# ST_LINK_V3E.net
KiCad netlist of a schematic drawn in Altium Designer
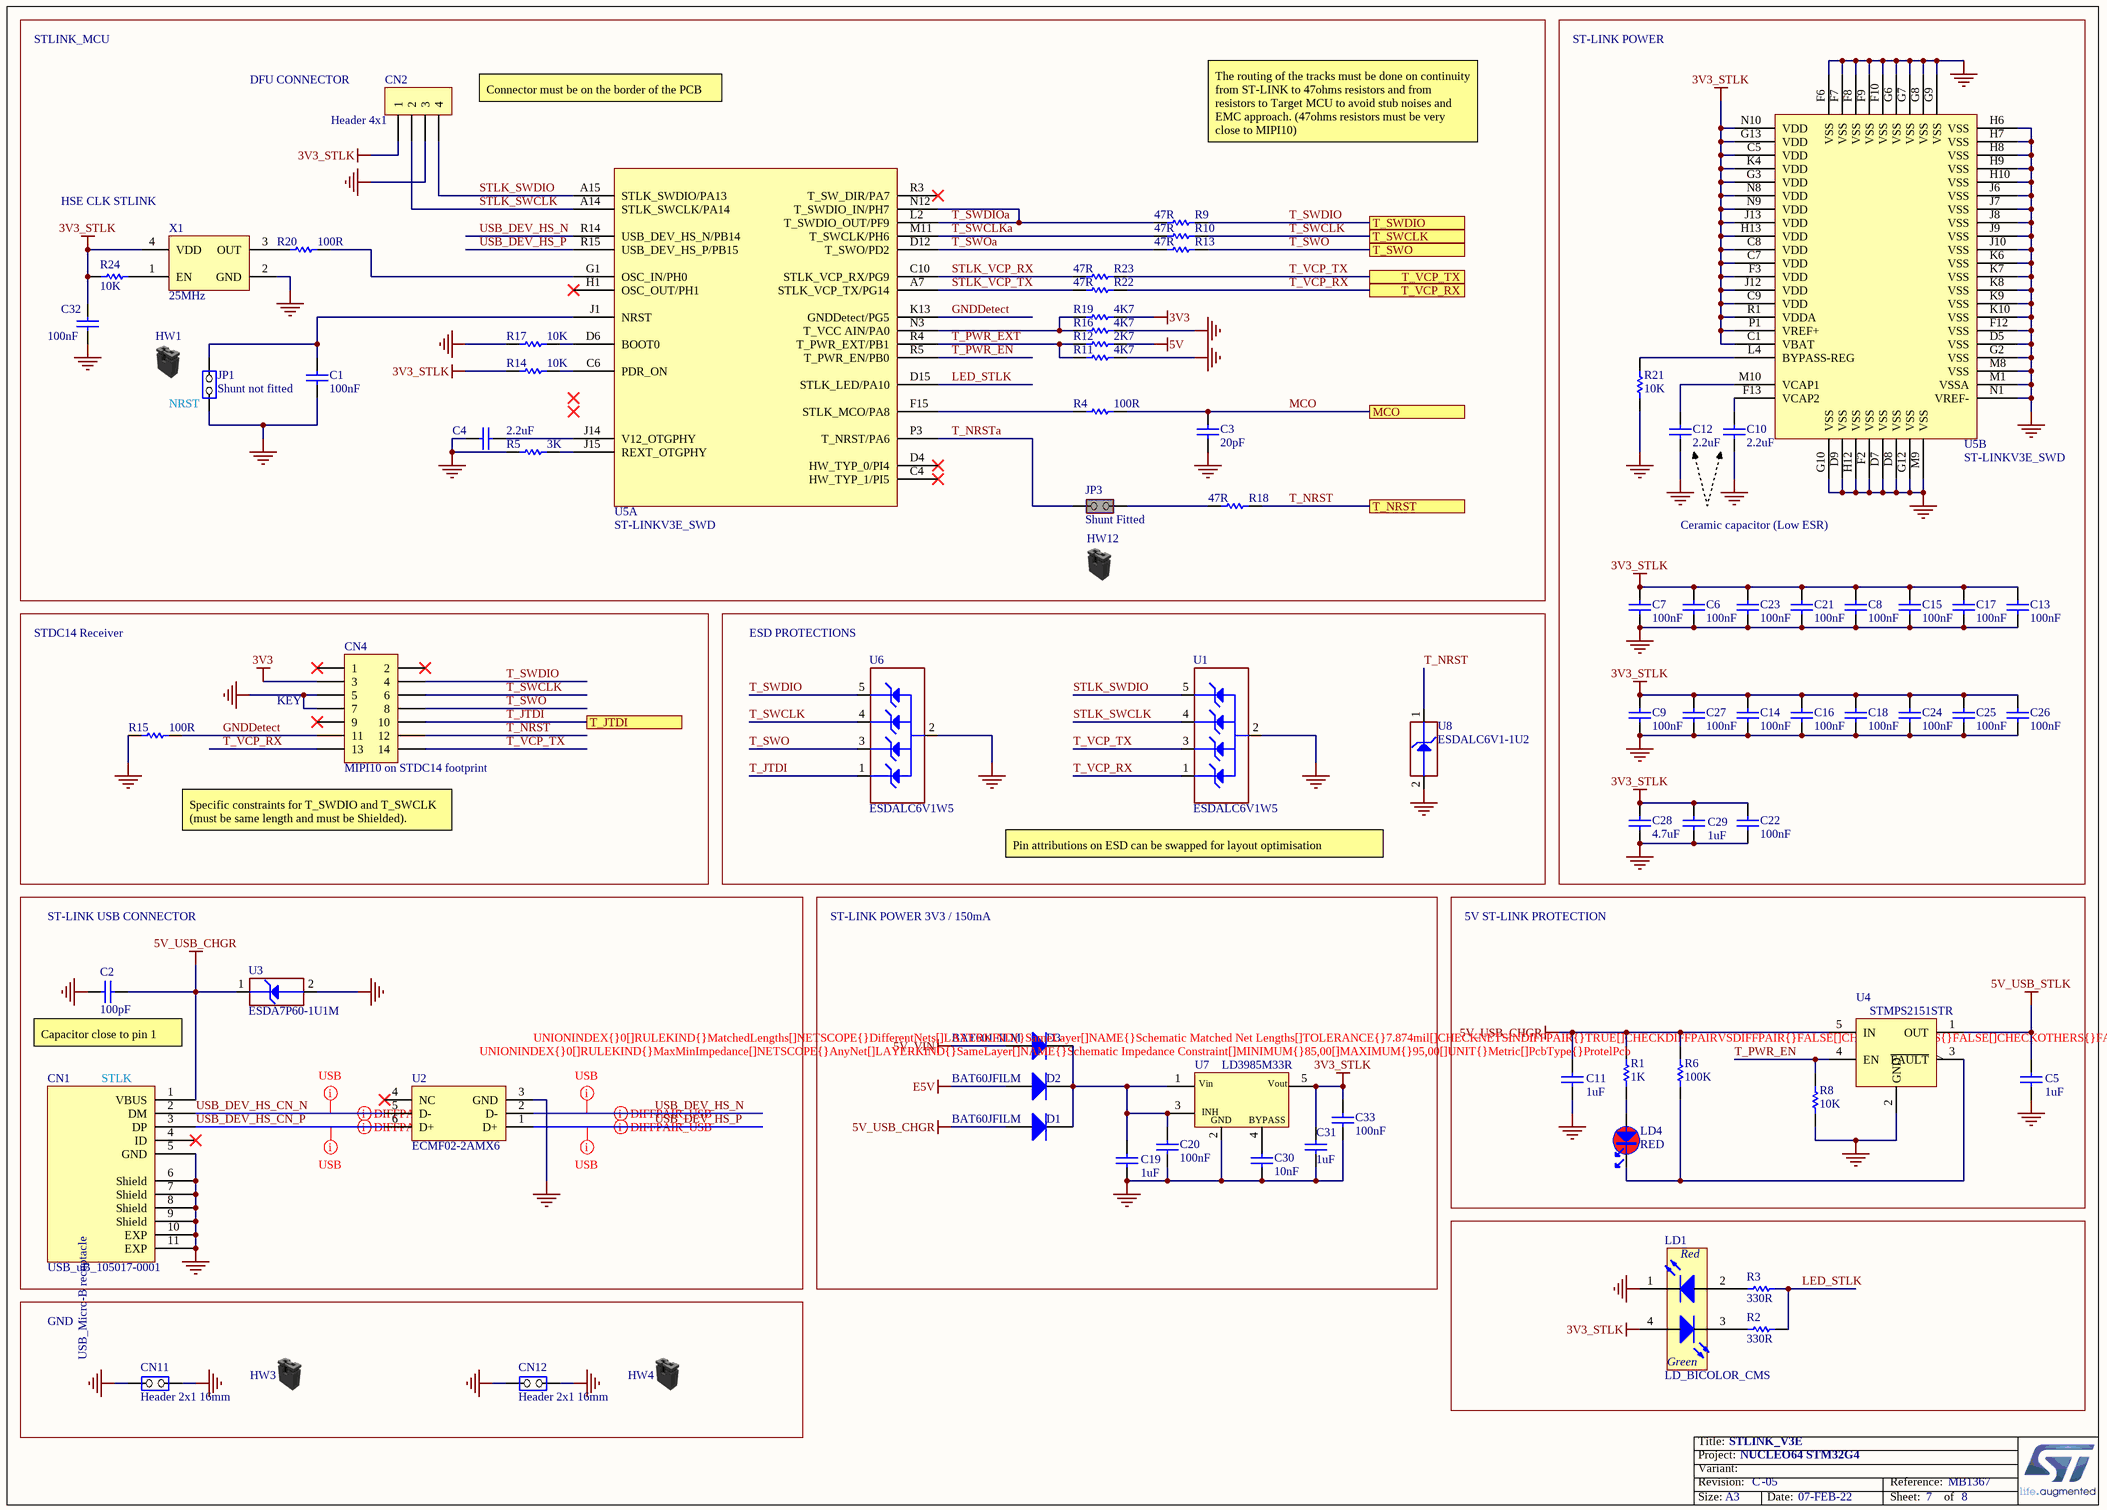
[diagram p0: ST_LINK_V3E.SchDoc]

(export (version "E")
  (design (tool "Eeschema 10.0.6"))
  (components
    (comp (ref "C1")
      (value "100nF")
      (footprint "C0402")
      (description "Capacitor, MLCC, 100nF, 16V, X7R, 10%, 0402, T=0,5mm")
      (fields
        (field (name "INTERNAL_PART_NUMBER") "MCD-00102")
        (field (name "MANUFACTURER_PART_NUMBER") "CC0402KRX7R7BB104")
      )
      (libsource (lib "MCD_PARTS_database") (part "Capacitor"))
    )
    (comp (ref "C2")
      (value "100pF")
      (footprint "C0402")
      (description "Capacitor, MLCC, 100pF, 50V, NPO, 5%, 0402, T=0,5mm")
      (fields
        (field (name "INTERNAL_PART_NUMBER") "MCD-00205")
        (field (name "MANUFACTURER_PART_NUMBER") "CC0402JRNPO9BN101")
      )
      (libsource (lib "MCD_PARTS_database") (part "Capacitor"))
    )
    (comp (ref "C3")
      (value "20pF")
      (footprint "C0402")
      (description "Capacitor, MLCC, 20pF, 50V, NPO, 5%, 0402, T=0,5mm")
      (fields
        (field (name "INTERNAL_PART_NUMBER") "MCD-00016")
        (field (name "MANUFACTURER_PART_NUMBER") "CC0402JRNPO9BN200")
      )
      (libsource (lib "MCD_PARTS_database") (part "Capacitor"))
    )
    (comp (ref "C4")
      (value "2.2uF")
      (footprint "C0603")
      (description "Capacitor, MLCC, 2.2uF, 10V, X5R, 10%, 0603, T=0,8mm")
      (fields
        (field (name "INTERNAL_PART_NUMBER") "MCD-00012")
        (field (name "MANUFACTURER_PART_NUMBER") "CC0603KRX5R6BB225")
      )
      (libsource (lib "MCD_PARTS_database") (part "Capacitor"))
    )
    (comp (ref "C5")
      (value "1uF")
      (footprint "C0603")
      (description "Capacitor, MLCC, 1uF, 16V, X5R, 10%, 0603, T=0,8mm")
      (fields
        (field (name "INTERNAL_PART_NUMBER") "MCD-00010")
        (field (name "MANUFACTURER_PART_NUMBER") "CC0603KRX5R7BB105")
      )
      (libsource (lib "MCD_PARTS_database") (part "Capacitor"))
    )
    (comp (ref "C6")
      (value "100nF")
      (footprint "C0402")
      (description "Capacitor, MLCC, 100nF, 16V, X7R, 10%, 0402, T=0,5mm")
      (fields
        (field (name "INTERNAL_PART_NUMBER") "MCD-00102")
        (field (name "MANUFACTURER_PART_NUMBER") "CC0402KRX7R7BB104")
      )
      (libsource (lib "MCD_PARTS_database") (part "Capacitor"))
    )
    (comp (ref "C7")
      (value "100nF")
      (footprint "C0402")
      (description "Capacitor, MLCC, 100nF, 16V, X7R, 10%, 0402, T=0,5mm")
      (fields
        (field (name "INTERNAL_PART_NUMBER") "MCD-00102")
        (field (name "MANUFACTURER_PART_NUMBER") "CC0402KRX7R7BB104")
      )
      (libsource (lib "MCD_PARTS_database") (part "Capacitor"))
    )
    (comp (ref "C8")
      (value "100nF")
      (footprint "C0402")
      (description "Capacitor, MLCC, 100nF, 16V, X7R, 10%, 0402, T=0,5mm")
      (fields
        (field (name "INTERNAL_PART_NUMBER") "MCD-00102")
        (field (name "MANUFACTURER_PART_NUMBER") "CC0402KRX7R7BB104")
      )
      (libsource (lib "MCD_PARTS_database") (part "Capacitor"))
    )
    (comp (ref "C9")
      (value "100nF")
      (footprint "C0402")
      (description "Capacitor, MLCC, 100nF, 16V, X7R, 10%, 0402, T=0,5mm")
      (fields
        (field (name "INTERNAL_PART_NUMBER") "MCD-00102")
        (field (name "MANUFACTURER_PART_NUMBER") "CC0402KRX7R7BB104")
      )
      (libsource (lib "MCD_PARTS_database") (part "Capacitor"))
    )
    (comp (ref "C10")
      (value "2.2uF")
      (footprint "C1206_H1P15")
      (description "Capacitor, MLCC, 2.2uF, 16V, X7R, 10%, 1206, T=1,15mm")
      (fields
        (field (name "INTERNAL_PART_NUMBER") "MCD-00008")
        (field (name "MANUFACTURER_PART_NUMBER") "CC1206KKX7R7BB225")
      )
      (libsource (lib "MCD_PARTS_database") (part "Capacitor"))
    )
    (comp (ref "C11")
      (value "1uF")
      (footprint "C0603")
      (description "Capacitor, MLCC, 1uF, 16V, X5R, 10%, 0603, T=0,8mm")
      (fields
        (field (name "INTERNAL_PART_NUMBER") "MCD-00010")
        (field (name "MANUFACTURER_PART_NUMBER") "CC0603KRX5R7BB105")
      )
      (libsource (lib "MCD_PARTS_database") (part "Capacitor"))
    )
    (comp (ref "C12")
      (value "2.2uF")
      (footprint "C1206_H1P15")
      (description "Capacitor, MLCC, 2.2uF, 16V, X7R, 10%, 1206, T=1,15mm")
      (fields
        (field (name "INTERNAL_PART_NUMBER") "MCD-00008")
        (field (name "MANUFACTURER_PART_NUMBER") "CC1206KKX7R7BB225")
      )
      (libsource (lib "MCD_PARTS_database") (part "Capacitor"))
    )
    (comp (ref "C13")
      (value "100nF")
      (footprint "C0402")
      (description "Capacitor, MLCC, 100nF, 16V, X7R, 10%, 0402, T=0,5mm")
      (fields
        (field (name "INTERNAL_PART_NUMBER") "MCD-00102")
        (field (name "MANUFACTURER_PART_NUMBER") "CC0402KRX7R7BB104")
      )
      (libsource (lib "MCD_PARTS_database") (part "Capacitor"))
    )
    (comp (ref "C14")
      (value "100nF")
      (footprint "C0402")
      (description "Capacitor, MLCC, 100nF, 16V, X7R, 10%, 0402, T=0,5mm")
      (fields
        (field (name "INTERNAL_PART_NUMBER") "MCD-00102")
        (field (name "MANUFACTURER_PART_NUMBER") "CC0402KRX7R7BB104")
      )
      (libsource (lib "MCD_PARTS_database") (part "Capacitor"))
    )
    (comp (ref "C15")
      (value "100nF")
      (footprint "C0402")
      (description "Capacitor, MLCC, 100nF, 16V, X7R, 10%, 0402, T=0,5mm")
      (fields
        (field (name "INTERNAL_PART_NUMBER") "MCD-00102")
        (field (name "MANUFACTURER_PART_NUMBER") "CC0402KRX7R7BB104")
      )
      (libsource (lib "MCD_PARTS_database") (part "Capacitor"))
    )
    (comp (ref "C16")
      (value "100nF")
      (footprint "C0402")
      (description "Capacitor, MLCC, 100nF, 16V, X7R, 10%, 0402, T=0,5mm")
      (fields
        (field (name "INTERNAL_PART_NUMBER") "MCD-00102")
        (field (name "MANUFACTURER_PART_NUMBER") "CC0402KRX7R7BB104")
      )
      (libsource (lib "MCD_PARTS_database") (part "Capacitor"))
    )
    (comp (ref "C17")
      (value "100nF")
      (footprint "C0402")
      (description "Capacitor, MLCC, 100nF, 16V, X7R, 10%, 0402, T=0,5mm")
      (fields
        (field (name "INTERNAL_PART_NUMBER") "MCD-00102")
        (field (name "MANUFACTURER_PART_NUMBER") "CC0402KRX7R7BB104")
      )
      (libsource (lib "MCD_PARTS_database") (part "Capacitor"))
    )
    (comp (ref "C18")
      (value "100nF")
      (footprint "C0402")
      (description "Capacitor, MLCC, 100nF, 16V, X7R, 10%, 0402, T=0,5mm")
      (fields
        (field (name "INTERNAL_PART_NUMBER") "MCD-00102")
        (field (name "MANUFACTURER_PART_NUMBER") "CC0402KRX7R7BB104")
      )
      (libsource (lib "MCD_PARTS_database") (part "Capacitor"))
    )
    (comp (ref "C19")
      (value "1uF")
      (footprint "C0603")
      (description "Capacitor, MLCC, 1uF, 16V, X5R, 10%, 0603, T=0,8mm")
      (fields
        (field (name "INTERNAL_PART_NUMBER") "MCD-00010")
        (field (name "MANUFACTURER_PART_NUMBER") "CC0603KRX5R7BB105")
      )
      (libsource (lib "MCD_PARTS_database") (part "Capacitor"))
    )
    (comp (ref "C20")
      (value "100nF")
      (footprint "C0402")
      (description "Capacitor, MLCC, 100nF, 16V, X7R, 10%, 0402, T=0,5mm")
      (fields
        (field (name "INTERNAL_PART_NUMBER") "MCD-00102")
        (field (name "MANUFACTURER_PART_NUMBER") "CC0402KRX7R7BB104")
      )
      (libsource (lib "MCD_PARTS_database") (part "Capacitor"))
    )
    (comp (ref "C21")
      (value "100nF")
      (footprint "C0402")
      (description "Capacitor, MLCC, 100nF, 16V, X7R, 10%, 0402, T=0,5mm")
      (fields
        (field (name "INTERNAL_PART_NUMBER") "MCD-00102")
        (field (name "MANUFACTURER_PART_NUMBER") "CC0402KRX7R7BB104")
      )
      (libsource (lib "MCD_PARTS_database") (part "Capacitor"))
    )
    (comp (ref "C22")
      (value "100nF")
      (footprint "C0402")
      (description "Capacitor, MLCC, 100nF, 16V, X7R, 10%, 0402, T=0,5mm")
      (fields
        (field (name "INTERNAL_PART_NUMBER") "MCD-00102")
        (field (name "MANUFACTURER_PART_NUMBER") "CC0402KRX7R7BB104")
      )
      (libsource (lib "MCD_PARTS_database") (part "Capacitor"))
    )
    (comp (ref "C23")
      (value "100nF")
      (footprint "C0402")
      (description "Capacitor, MLCC, 100nF, 16V, X7R, 10%, 0402, T=0,5mm")
      (fields
        (field (name "INTERNAL_PART_NUMBER") "MCD-00102")
        (field (name "MANUFACTURER_PART_NUMBER") "CC0402KRX7R7BB104")
      )
      (libsource (lib "MCD_PARTS_database") (part "Capacitor"))
    )
    (comp (ref "C24")
      (value "100nF")
      (footprint "C0402")
      (description "Capacitor, MLCC, 100nF, 16V, X7R, 10%, 0402, T=0,5mm")
      (fields
        (field (name "INTERNAL_PART_NUMBER") "MCD-00102")
        (field (name "MANUFACTURER_PART_NUMBER") "CC0402KRX7R7BB104")
      )
      (libsource (lib "MCD_PARTS_database") (part "Capacitor"))
    )
    (comp (ref "C25")
      (value "100nF")
      (footprint "C0402")
      (description "Capacitor, MLCC, 100nF, 16V, X7R, 10%, 0402, T=0,5mm")
      (fields
        (field (name "INTERNAL_PART_NUMBER") "MCD-00102")
        (field (name "MANUFACTURER_PART_NUMBER") "CC0402KRX7R7BB104")
      )
      (libsource (lib "MCD_PARTS_database") (part "Capacitor"))
    )
    (comp (ref "C26")
      (value "100nF")
      (footprint "C0402")
      (description "Capacitor, MLCC, 100nF, 16V, X7R, 10%, 0402, T=0,5mm")
      (fields
        (field (name "INTERNAL_PART_NUMBER") "MCD-00102")
        (field (name "MANUFACTURER_PART_NUMBER") "CC0402KRX7R7BB104")
      )
      (libsource (lib "MCD_PARTS_database") (part "Capacitor"))
    )
    (comp (ref "C27")
      (value "100nF")
      (footprint "C0402")
      (description "Capacitor, MLCC, 100nF, 16V, X7R, 10%, 0402, T=0,5mm")
      (fields
        (field (name "INTERNAL_PART_NUMBER") "MCD-00102")
        (field (name "MANUFACTURER_PART_NUMBER") "CC0402KRX7R7BB104")
      )
      (libsource (lib "MCD_PARTS_database") (part "Capacitor"))
    )
    (comp (ref "C28")
      (value "4.7uF")
      (footprint "C0603")
      (description "Capacitor, MLCC, 4.7uF, 16V, X5R, 10%, 0603, T=0.8mm")
      (fields
        (field (name "INTERNAL_PART_NUMBER") "MCD-00009")
        (field (name "MANUFACTURER_PART_NUMBER") "CC0603KRX5R7BB475")
      )
      (libsource (lib "MCD_PARTS_database") (part "Capacitor"))
    )
    (comp (ref "C29")
      (value "1uF")
      (footprint "C0603")
      (description "Capacitor, MLCC, 1uF, 16V, X5R, 10%, 0603, T=0,8mm")
      (fields
        (field (name "INTERNAL_PART_NUMBER") "MCD-00010")
        (field (name "MANUFACTURER_PART_NUMBER") "CC0603KRX5R7BB105")
      )
      (libsource (lib "MCD_PARTS_database") (part "Capacitor"))
    )
    (comp (ref "C30")
      (value "10nF")
      (footprint "C0402")
      (description "Capacitor, MLCC, 10nF, 16V, X7R, 10%, 0402, T=0.5mm")
      (fields
        (field (name "INTERNAL_PART_NUMBER") "MCD-00011")
        (field (name "MANUFACTURER_PART_NUMBER") "CC0402KRX7R7BB103")
      )
      (libsource (lib "MCD_PARTS_database") (part "Capacitor"))
    )
    (comp (ref "C31")
      (value "1uF")
      (footprint "C0603")
      (description "Capacitor, MLCC, 1uF, 16V, X5R, 10%, 0603, T=0,8mm")
      (fields
        (field (name "INTERNAL_PART_NUMBER") "MCD-00010")
        (field (name "MANUFACTURER_PART_NUMBER") "CC0603KRX5R7BB105")
      )
      (libsource (lib "MCD_PARTS_database") (part "Capacitor"))
    )
    (comp (ref "C32")
      (value "100nF")
      (footprint "C0402")
      (description "Capacitor, MLCC, 100nF, 16V, X7R, 10%, 0402, T=0,5mm")
      (fields
        (field (name "INTERNAL_PART_NUMBER") "MCD-00102")
        (field (name "MANUFACTURER_PART_NUMBER") "CC0402KRX7R7BB104")
      )
      (libsource (lib "MCD_PARTS_database") (part "Capacitor"))
    )
    (comp (ref "C33")
      (value "100nF")
      (footprint "C0402")
      (description "Capacitor, MLCC, 100nF, 16V, X7R, 10%, 0402, T=0,5mm")
      (fields
        (field (name "INTERNAL_PART_NUMBER") "MCD-00102")
        (field (name "MANUFACTURER_PART_NUMBER") "CC0402KRX7R7BB104")
      )
      (libsource (lib "MCD_PARTS_database") (part "Capacitor"))
    )
    (comp (ref "CN1")
      (value "USB_uB_105017-0001")
      (footprint "CON_USBMICROB_MOLEX_105017-0001_H2P90")
      (description "USB-MICRO-B, 0.65mm, RA, SMT, Bottom Mount,")
      (fields
        (field (name "INTERNAL_PART_NUMBER") "MCD-00028")
        (field (name "MANUFACTURER_PART_NUMBER") "1050170001")
      )
      (libsource (lib "MCD_PARTS_database") (part "USB_uB_105017.0001"))
    )
    (comp (ref "CN2")
      (value "Header 4x1")
      (footprint "CON_SAMTEC_TSW-104-07-G-S")
      (description "Header, 4x1, 2,54mm, VR, TH, Height 5.84mm/2.54mm")
      (fields
        (field (name "INTERNAL_PART_NUMBER") "MCD-00029")
        (field (name "MANUFACTURER_PART_NUMBER") "TSW-104-07-x-S")
      )
      (libsource (lib "MCD_PARTS_database") (part "Header 4x1"))
    )
    (comp (ref "CN4")
      (value "MIPI10 on STDC14 footprint")
      (footprint "CON_STDC14_Receiver_MEDIUM_WITH_MIPI10_3D")
      (fields
        (field (name "INTERNAL_PART_NUMBER") "MCD-01226")
        (field (name "MANUFACTURER_PART_NUMBER") "FTSH-105-01-L-DV-K")
        (field (name "MANUFACTURER") "SAMTEC")
      )
      (libsource (lib "MCD_PARTS_database") (part "Header 7x2"))
    )
    (comp (ref "CN11")
      (value "Header 2x1 16mm")
      (footprint "CON_SAMTEC_TSW-102-09-X-S")
      (description "Header, 2x1, 2,54mm, VR, TH, Height 5.84mm/10.16mm")
      (fields
        (field (name "INTERNAL_PART_NUMBER") "MCD-00214")
        (field (name "MANUFACTURER_PART_NUMBER") "TSW-102-09-x-S")
      )
      (libsource (lib "MCD_PARTS_database") (part "Jumper_Header 2x1"))
    )
    (comp (ref "CN12")
      (value "Header 2x1 16mm")
      (footprint "CON_SAMTEC_TSW-102-09-X-S")
      (description "Header, 2x1, 2,54mm, VR, TH, Height 5.84mm/10.16mm")
      (fields
        (field (name "INTERNAL_PART_NUMBER") "MCD-00214")
        (field (name "MANUFACTURER_PART_NUMBER") "TSW-102-09-x-S")
      )
      (libsource (lib "MCD_PARTS_database") (part "Jumper_Header 2x1"))
    )
    (comp (ref "D1")
      (value "BAT60JFILM")
      (footprint "DIO_SOD323")
      (fields
        (field (name "INTERNAL_PART_NUMBER") "MCD-00034")
        (field (name "MANUFACTURER") "STMICROELECTRONICS")
      )
      (libsource (lib "MCD_PARTS_database") (part "BAT60JFILM"))
    )
    (comp (ref "D2")
      (value "BAT60JFILM")
      (footprint "DIO_SOD323")
      (fields
        (field (name "INTERNAL_PART_NUMBER") "MCD-00034")
        (field (name "MANUFACTURER") "STMICROELECTRONICS")
      )
      (libsource (lib "MCD_PARTS_database") (part "BAT60JFILM"))
    )
    (comp (ref "D3")
      (value "BAT60JFILM")
      (footprint "DIO_SOD323")
      (fields
        (field (name "INTERNAL_PART_NUMBER") "MCD-00034")
        (field (name "MANUFACTURER") "STMICROELECTRONICS")
      )
      (libsource (lib "MCD_PARTS_database") (part "BAT60JFILM"))
    )
    (comp (ref "HW1")
      (value "~")
      (description "SHUNT 2.54mm BLACK")
      (fields
        (field (name "INTERNAL_PART_NUMBER") "MCD-00043")
        (field (name "MANUFACTURER_PART_NUMBER") "SNT-100-BK-G")
      )
      (libsource (lib "MCD_PARTS_database") (part "Shunt Black 2.54mm"))
    )
    (comp (ref "HW3")
      (value "~")
      (description "SHUNT 2.54mm BLACK")
      (fields
        (field (name "INTERNAL_PART_NUMBER") "MCD-00043")
        (field (name "MANUFACTURER_PART_NUMBER") "SNT-100-BK-G")
      )
      (libsource (lib "MCD_PARTS_database") (part "Shunt Black 2.54mm"))
    )
    (comp (ref "HW4")
      (value "~")
      (description "SHUNT 2.54mm BLACK")
      (fields
        (field (name "INTERNAL_PART_NUMBER") "MCD-00043")
        (field (name "MANUFACTURER_PART_NUMBER") "SNT-100-BK-G")
      )
      (libsource (lib "MCD_PARTS_database") (part "Shunt Black 2.54mm"))
    )
    (comp (ref "HW12")
      (value "~")
      (description "SHUNT 2.54mm BLACK")
      (fields
        (field (name "INTERNAL_PART_NUMBER") "MCD-00043")
        (field (name "MANUFACTURER_PART_NUMBER") "SNT-100-BK-G")
      )
      (libsource (lib "MCD_PARTS_database") (part "Shunt Black 2.54mm"))
    )
    (comp (ref "JP1")
      (value "Shunt not fitted")
      (footprint "CON_SAMTEC_TSW-102-07-G-S")
      (description "Header, 2x1, 2,54mm, VR, TH, Height 5.84mm/2.54mm")
      (fields
        (field (name "INTERNAL_PART_NUMBER") "MCD-00045")
        (field (name "MANUFACTURER_PART_NUMBER") "TSW-102-07-x-S")
      )
      (libsource (lib "MCD_PARTS_database") (part "Jumper_Header 2x1"))
    )
    (comp (ref "JP3")
      (value "Shunt Fitted")
      (footprint "CON_SAMTEC_TSW-102-07-G-S")
      (description "Header, 2x1, 2,54mm, VR, TH, Height 5.84mm/2.54mm - Shunt Fitted by default")
      (fields
        (field (name "INTERNAL_PART_NUMBER") "MCD-00683")
        (field (name "MANUFACTURER_PART_NUMBER") "TSW-102-07-x-S")
      )
      (libsource (lib "MCD_PARTS_database") (part "Jumper_Header 2x1 Fitted"))
    )
    (comp (ref "LD1")
      (value "LD_BICOLOR_CMS")
      (footprint "LED_BI-GR_HSMF-A201-A00J1")
      (description "LED Bicolor")
      (fields (field (name "INTERNAL_PART_NUMBER") "MCD-02402") (field (name "MANUFACTURER") "EVERLIGHT"))
      (libsource (lib "MCD_PARTS_database") (part "LD_BICOLOR_CMS"))
    )
    (comp (ref "LD4")
      (value "RED")
      (footprint "LED_0603_RED_H0P4")
      (description "LED, Red, VF : Min=1.7V , Max=2.2V, IF : 25mA, 0603 SMD")
      (fields (field (name "INTERNAL_PART_NUMBER") "MCD-02787") (field (name "MANUFACTURER") "EVERLIGHT"))
      (libsource (lib "MCD_PARTS_database") (part "LED_red"))
    )
    (comp (ref "R1")
      (value "1K")
      (footprint "R0603")
      (description "Resistor,1K,0603,1%,1/10W")
      (fields
        (field (name "INTERNAL_PART_NUMBER") "MCD-00070")
        (field (name "MANUFACTURER_PART_NUMBER") "RC0603FR-071KL")
      )
      (libsource (lib "MCD_PARTS_database") (part "Resistor"))
    )
    (comp (ref "R2")
      (value "330R")
      (footprint "R0603")
      (description "Resistor,330R,0603,1%,1/10W")
      (fields
        (field (name "INTERNAL_PART_NUMBER") "MCD-00197")
        (field (name "MANUFACTURER_PART_NUMBER") "RC0603FR-07330RL")
      )
      (libsource (lib "MCD_PARTS_database") (part "Resistor"))
    )
    (comp (ref "R3")
      (value "330R")
      (footprint "R0603")
      (description "Resistor,330R,0603,1%,1/10W")
      (fields
        (field (name "INTERNAL_PART_NUMBER") "MCD-00197")
        (field (name "MANUFACTURER_PART_NUMBER") "RC0603FR-07330RL")
      )
      (libsource (lib "MCD_PARTS_database") (part "Resistor"))
    )
    (comp (ref "R4")
      (value "100R")
      (footprint "R0402")
      (description "Resistor,100R,0402,1%,1/16W")
      (fields
        (field (name "INTERNAL_PART_NUMBER") "MCD-00119")
        (field (name "MANUFACTURER_PART_NUMBER") "RC0402FR-07100RL")
      )
      (libsource (lib "MCD_PARTS_database") (part "Resistor"))
    )
    (comp (ref "R5")
      (value "3K")
      (footprint "R0402")
      (description "Resistor,3K,0402,1%,1/16W")
      (fields
        (field (name "INTERNAL_PART_NUMBER") "MCD-00185")
        (field (name "MANUFACTURER_PART_NUMBER") "RC0402FR-073KL")
      )
      (libsource (lib "MCD_PARTS_database") (part "Resistor"))
    )
    (comp (ref "R6")
      (value "100K")
      (footprint "R0603")
      (description "Resistor,100K,0603,1%,1/10W")
      (fields
        (field (name "INTERNAL_PART_NUMBER") "MCD-00223")
        (field (name "MANUFACTURER_PART_NUMBER") "RC0603FR-07100KL")
      )
      (libsource (lib "MCD_PARTS_database") (part "Resistor"))
    )
    (comp (ref "R8")
      (value "10K")
      (footprint "R0603")
      (description "Resistor,10K,0603,1%,1/10W")
      (fields
        (field (name "INTERNAL_PART_NUMBER") "MCD-00220")
        (field (name "MANUFACTURER_PART_NUMBER") "RC0603FR-0710KL")
      )
      (libsource (lib "MCD_PARTS_database") (part "Resistor"))
    )
    (comp (ref "R9")
      (value "47R")
      (footprint "R0402")
      (description "Resistor,47R,0402,1%,1/16W")
      (fields
        (field (name "INTERNAL_PART_NUMBER") "MCD-00481")
        (field (name "MANUFACTURER_PART_NUMBER") "RC0402FR-0747RL")
      )
      (libsource (lib "MCD_PARTS_database") (part "Resistor"))
    )
    (comp (ref "R10")
      (value "47R")
      (footprint "R0402")
      (description "Resistor,47R,0402,1%,1/16W")
      (fields
        (field (name "INTERNAL_PART_NUMBER") "MCD-00481")
        (field (name "MANUFACTURER_PART_NUMBER") "RC0402FR-0747RL")
      )
      (libsource (lib "MCD_PARTS_database") (part "Resistor"))
    )
    (comp (ref "R11")
      (value "4K7")
      (footprint "R0402")
      (description "Resistor,4K7,0402,1%,1/16W")
      (fields
        (field (name "INTERNAL_PART_NUMBER") "MCD-00065")
        (field (name "MANUFACTURER_PART_NUMBER") "RC0402FR-074K7L")
      )
      (libsource (lib "MCD_PARTS_database") (part "Resistor"))
    )
    (comp (ref "R12")
      (value "2K7")
      (footprint "R0402")
      (description "Resistor,2K7,0402,1%,1/16W")
      (fields
        (field (name "INTERNAL_PART_NUMBER") "MCD-00055")
        (field (name "MANUFACTURER_PART_NUMBER") "RC0402FR-072K7L")
      )
      (libsource (lib "MCD_PARTS_database") (part "Resistor"))
    )
    (comp (ref "R13")
      (value "47R")
      (footprint "R0402")
      (description "Resistor,47R,0402,1%,1/16W")
      (fields
        (field (name "INTERNAL_PART_NUMBER") "MCD-00481")
        (field (name "MANUFACTURER_PART_NUMBER") "RC0402FR-0747RL")
      )
      (libsource (lib "MCD_PARTS_database") (part "Resistor"))
    )
    (comp (ref "R14")
      (value "10K")
      (footprint "R0402")
      (description "Resistor,10K,0402,1%,1/16W")
      (fields
        (field (name "INTERNAL_PART_NUMBER") "MCD-00053")
        (field (name "MANUFACTURER_PART_NUMBER") "RC0402FR-0710KL")
      )
      (libsource (lib "MCD_PARTS_database") (part "Resistor"))
    )
    (comp (ref "R15")
      (value "100R")
      (footprint "R0402")
      (description "Resistor,100R,0402,1%,1/16W")
      (fields
        (field (name "INTERNAL_PART_NUMBER") "MCD-00119")
        (field (name "MANUFACTURER_PART_NUMBER") "RC0402FR-07100RL")
      )
      (libsource (lib "MCD_PARTS_database") (part "Resistor"))
    )
    (comp (ref "R16")
      (value "4K7")
      (footprint "R0402")
      (description "Resistor,4K7,0402,1%,1/16W")
      (fields
        (field (name "INTERNAL_PART_NUMBER") "MCD-00065")
        (field (name "MANUFACTURER_PART_NUMBER") "RC0402FR-074K7L")
      )
      (libsource (lib "MCD_PARTS_database") (part "Resistor"))
    )
    (comp (ref "R17")
      (value "10K")
      (footprint "R0402")
      (description "Resistor,10K,0402,1%,1/16W")
      (fields
        (field (name "INTERNAL_PART_NUMBER") "MCD-00053")
        (field (name "MANUFACTURER_PART_NUMBER") "RC0402FR-0710KL")
      )
      (libsource (lib "MCD_PARTS_database") (part "Resistor"))
    )
    (comp (ref "R18")
      (value "47R")
      (footprint "R0402")
      (description "Resistor,47R,0402,1%,1/16W")
      (fields
        (field (name "INTERNAL_PART_NUMBER") "MCD-00481")
        (field (name "MANUFACTURER_PART_NUMBER") "RC0402FR-0747RL")
      )
      (libsource (lib "MCD_PARTS_database") (part "Resistor"))
    )
    (comp (ref "R19")
      (value "4K7")
      (footprint "R0402")
      (description "Resistor,4K7,0402,1%,1/16W")
      (fields
        (field (name "INTERNAL_PART_NUMBER") "MCD-00065")
        (field (name "MANUFACTURER_PART_NUMBER") "RC0402FR-074K7L")
      )
      (libsource (lib "MCD_PARTS_database") (part "Resistor"))
    )
    (comp (ref "R20")
      (value "100R")
      (footprint "R0402")
      (description "Resistor,100R,0402,1%,1/16W")
      (fields
        (field (name "INTERNAL_PART_NUMBER") "MCD-00119")
        (field (name "MANUFACTURER_PART_NUMBER") "RC0402FR-07100RL")
      )
      (libsource (lib "MCD_PARTS_database") (part "Resistor"))
    )
    (comp (ref "R21")
      (value "10K")
      (footprint "R0402")
      (description "Resistor,10K,0402,1%,1/16W")
      (fields
        (field (name "INTERNAL_PART_NUMBER") "MCD-00053")
        (field (name "MANUFACTURER_PART_NUMBER") "RC0402FR-0710KL")
      )
      (libsource (lib "MCD_PARTS_database") (part "Resistor"))
    )
    (comp (ref "R22")
      (value "47R")
      (footprint "R0402")
      (description "Resistor,47R,0402,1%,1/16W")
      (fields
        (field (name "INTERNAL_PART_NUMBER") "MCD-00481")
        (field (name "MANUFACTURER_PART_NUMBER") "RC0402FR-0747RL")
      )
      (libsource (lib "MCD_PARTS_database") (part "Resistor"))
    )
    (comp (ref "R23")
      (value "47R")
      (footprint "R0402")
      (description "Resistor,47R,0402,1%,1/16W")
      (fields
        (field (name "INTERNAL_PART_NUMBER") "MCD-00481")
        (field (name "MANUFACTURER_PART_NUMBER") "RC0402FR-0747RL")
      )
      (libsource (lib "MCD_PARTS_database") (part "Resistor"))
    )
    (comp (ref "R24")
      (value "10K")
      (footprint "R0402")
      (description "Resistor,10K,0402,1%,1/16W")
      (fields
        (field (name "INTERNAL_PART_NUMBER") "MCD-00053")
        (field (name "MANUFACTURER_PART_NUMBER") "RC0402FR-0710KL")
      )
      (libsource (lib "MCD_PARTS_database") (part "Resistor"))
    )
    (comp (ref "U1")
      (value "ESDALC6V1W5")
      (footprint "ESD_SOT323-5L")
      (description "Dual Transil array for ESD protection")
      (fields
        (field (name "INTERNAL_PART_NUMBER") "MCD-00136")
        (field (name "MANUFACTURER") "STMICROELECTRONICS")
      )
      (libsource (lib "MCD_PARTS_database") (part "ESDALC6V1W5"))
    )
    (comp (ref "U2")
      (value "ECMF02-2AMX6")
      (footprint "ESD_QFN-6L_1P7X1P5_P050")
      (description "Common mode filter with ESD protection for USB 2.0 interface")
      (fields
        (field (name "INTERNAL_PART_NUMBER") "MCD-00649")
        (field (name "MANUFACTURER") "STMICROELECTRONICS")
      )
      (libsource (lib "MCD_PARTS_database") (part "ECMF02-2AMX6"))
    )
    (comp (ref "U3")
      (value "ESDA7P60-1U1M")
      (footprint "ESD_QFN2_1P6X1_P125")
      (description "High power transient voltage suppressor, 7V breakdown")
      (fields
        (field (name "INTERNAL_PART_NUMBER") "MCD-00251")
        (field (name "MANUFACTURER") "STMICROELECTRONICS")
      )
      (libsource (lib "") (part "ESD-TRANSIL_1"))
    )
    (comp (ref "U4")
      (value "STMPS2151STR")
      (footprint "MOS_SOT23-5L")
      (description "500mA, Enhanced single channel power switches with active high enable pin")
      (fields
        (field (name "INTERNAL_PART_NUMBER") "MCD-00159")
        (field (name "MANUFACTURER") "STMICROELECTRONICS")
      )
      (libsource (lib "MCD_PARTS_database") (part "STMPS2151STR"))
    )
    (comp (ref "U5")
      (value "ST-LINKV3E_SWD")
      (footprint "ICC_UFBGA201_176+25_10X10_P065")
      (description "STM32F723IEK  (STM32F7) BGA176")
      (fields
        (field (name "INTERNAL_PART_NUMBER") "MCD-00596")
        (field (name "MANUFACTURER_PART_NUMBER") "STM32F723IEK6")
      )
      (libsource (lib "MCD_PARTS_database") (part "ST-LINKV3E_SWD"))
    )
    (comp (ref "U6")
      (value "ESDALC6V1W5")
      (footprint "ESD_SOT323-5L")
      (description "Dual Transil array for ESD protection")
      (fields
        (field (name "INTERNAL_PART_NUMBER") "MCD-00136")
        (field (name "MANUFACTURER") "STMICROELECTRONICS")
      )
      (libsource (lib "MCD_PARTS_database") (part "ESDALC6V1W5"))
    )
    (comp (ref "U7")
      (value "LD3985M33R")
      (footprint "REG_SOT23-5L")
      (description "Ultra low drop-low noise BiCMOS voltage, regulators low ESR capacitors compatible")
      (fields
        (field (name "INTERNAL_PART_NUMBER") "MCD-00086")
        (field (name "MANUFACTURER") "STMICROELECTRONICS")
      )
      (libsource (lib "MCD_PARTS_database") (part "LD3985M33R"))
    )
    (comp (ref "U8")
      (value "ESDALC6V1-1U2")
      (footprint "ESD_ST0201")
      (description "ESD protection 6V1")
      (fields
        (field (name "INTERNAL_PART_NUMBER") "MCD-00170")
        (field (name "MANUFACTURER") "STMICROELECTRONICS")
      )
      (libsource (lib "MCD_PARTS_database") (part "ESD-TRANSIL"))
    )
    (comp (ref "X1")
      (value "25MHz")
      (footprint "OSC_NDK_NZ2520SB_4P")
      (description "Oscillator 25.00Mhz, -+50PPM, 3.3V, Temp -55 to +125°C")
      (fields
        (field (name "INTERNAL_PART_NUMBER") "MCD-00597")
        (field (name "MANUFACTURER_PART_NUMBER") "NZ2520SB 25MHz END4869B")
      )
      (libsource (lib "MCD_PARTS_database") (part "Oscillator_4pins"))
    )
  )
  (nets
    (net (code "1") (name "/GNDDetect") (class "Default")
      (node (ref "CN4") (pin "11") (pinfunction "11_11") (pintype "passive"))
      (node (ref "R15") (pin "2") (pinfunction "2_2") (pintype "passive"))
      (node (ref "U5") (pin "K13") (pinfunction "GNDDetect/PG5_K13") (pintype "passive"))
    )
    (net (code "2") (name "/LED_STLK") (class "Default")
      (node (ref "R2") (pin "2") (pinfunction "2_2") (pintype "passive"))
      (node (ref "R3") (pin "2") (pinfunction "2_2") (pintype "passive"))
      (node (ref "U5") (pin "D15") (pinfunction "STLK_LED/PA10_D15") (pintype "passive"))
    )
    (net (code "3") (name "/MCO") (class "Default")
      (node (ref "C3") (pin "2") (pinfunction "2_2") (pintype "passive"))
      (node (ref "R4") (pin "2") (pinfunction "2_2") (pintype "passive"))
    )
    (net (code "4") (name "/STLK_SWCLK") (class "Default")
      (node (ref "CN2") (pin "2") (pinfunction "2_2") (pintype "passive"))
      (node (ref "U1") (pin "4") (pinfunction "IO3_4") (pintype "passive"))
      (node (ref "U5") (pin "A14") (pinfunction "STLK_SWCLK/PA14_A14") (pintype "passive"))
    )
    (net (code "5") (name "/STLK_SWDIO") (class "Default")
      (node (ref "CN2") (pin "4") (pinfunction "4_4") (pintype "passive"))
      (node (ref "U1") (pin "5") (pinfunction "IO4_5") (pintype "passive"))
      (node (ref "U5") (pin "A15") (pinfunction "STLK_SWDIO/PA13_A15") (pintype "passive"))
    )
    (net (code "6") (name "/STLK_VCP_RX") (class "Default")
      (node (ref "R23") (pin "1") (pinfunction "1_1") (pintype "passive"))
      (node (ref "U5") (pin "C10") (pinfunction "STLK_VCP_RX/PG9_C10") (pintype "passive"))
    )
    (net (code "7") (name "/STLK_VCP_TX") (class "Default")
      (node (ref "R22") (pin "1") (pinfunction "1_1") (pintype "passive"))
      (node (ref "U5") (pin "A7") (pinfunction "STLK_VCP_TX/PG14_A7") (pintype "passive"))
    )
    (net (code "8") (name "/T_JTDI") (class "Default")
      (node (ref "CN4") (pin "10") (pinfunction "10_10") (pintype "passive"))
      (node (ref "U6") (pin "1") (pinfunction "IO1_1") (pintype "passive"))
    )
    (net (code "9") (name "/T_NRST") (class "Default")
      (node (ref "CN4") (pin "12") (pinfunction "12_12") (pintype "passive"))
      (node (ref "R18") (pin "2") (pinfunction "2_2") (pintype "passive"))
      (node (ref "U8") (pin "1") (pinfunction "IO1_1") (pintype "passive"))
    )
    (net (code "10") (name "/T_NRSTa") (class "Default")
      (node (ref "JP3") (pin "1") (pinfunction "COMMON_1") (pintype "passive"))
      (node (ref "U5") (pin "P3") (pinfunction "T_NRST/PA6_P3") (pintype "passive"))
    )
    (net (code "11") (name "/T_PWR_EN") (class "Default")
      (node (ref "R8") (pin "1") (pinfunction "1_1") (pintype "passive"))
      (node (ref "U4") (pin "4") (pinfunction "EN_4") (pintype "passive"))
      (node (ref "U5") (pin "R5") (pinfunction "T_PWR_EN/PB0_R5") (pintype "passive"))
    )
    (net (code "12") (name "/T_PWR_EXT") (class "Default")
      (node (ref "R11") (pin "2") (pinfunction "2_2") (pintype "passive"))
      (node (ref "R12") (pin "2") (pinfunction "2_2") (pintype "passive"))
      (node (ref "U5") (pin "R4") (pinfunction "T_PWR_EXT/PB1_R4") (pintype "passive"))
    )
    (net (code "13") (name "/T_SWCLK") (class "Default")
      (node (ref "CN4") (pin "6") (pinfunction "6_6") (pintype "passive"))
      (node (ref "R10") (pin "2") (pinfunction "2_2") (pintype "passive"))
      (node (ref "U6") (pin "4") (pinfunction "IO3_4") (pintype "passive"))
    )
    (net (code "14") (name "/T_SWCLKa") (class "Default")
      (node (ref "R10") (pin "1") (pinfunction "1_1") (pintype "passive"))
      (node (ref "U5") (pin "M11") (pinfunction "T_SWCLK/PH6_M11") (pintype "passive"))
    )
    (net (code "15") (name "/T_SWDIO") (class "Default")
      (node (ref "CN4") (pin "4") (pinfunction "4_4") (pintype "passive"))
      (node (ref "R9") (pin "2") (pinfunction "2_2") (pintype "passive"))
      (node (ref "U6") (pin "5") (pinfunction "IO4_5") (pintype "passive"))
    )
    (net (code "16") (name "/T_SWDIOa") (class "Default")
      (node (ref "R9") (pin "1") (pinfunction "1_1") (pintype "passive"))
      (node (ref "U5") (pin "L2") (pinfunction "T_SWDIO_OUT/PF9_L2") (pintype "passive"))
      (node (ref "U5") (pin "N12") (pinfunction "T_SWDIO_IN/PH7_N12") (pintype "passive"))
    )
    (net (code "17") (name "/T_SWO") (class "Default")
      (node (ref "CN4") (pin "8") (pinfunction "8_8") (pintype "passive"))
      (node (ref "R13") (pin "2") (pinfunction "2_2") (pintype "passive"))
      (node (ref "U6") (pin "3") (pinfunction "IO2_3") (pintype "passive"))
    )
    (net (code "18") (name "/T_SWOa") (class "Default")
      (node (ref "R13") (pin "1") (pinfunction "1_1") (pintype "passive"))
      (node (ref "U5") (pin "D12") (pinfunction "T_SWO/PD2_D12") (pintype "passive"))
    )
    (net (code "19") (name "/T_VCP_RX") (class "Default")
      (node (ref "CN4") (pin "13") (pinfunction "13_13") (pintype "passive"))
      (node (ref "R22") (pin "2") (pinfunction "2_2") (pintype "passive"))
      (node (ref "U1") (pin "1") (pinfunction "IO1_1") (pintype "passive"))
    )
    (net (code "20") (name "/T_VCP_TX") (class "Default")
      (node (ref "CN4") (pin "14") (pinfunction "14_14") (pintype "passive"))
      (node (ref "R23") (pin "2") (pinfunction "2_2") (pintype "passive"))
      (node (ref "U1") (pin "3") (pinfunction "IO2_3") (pintype "passive"))
    )
    (net (code "21") (name "/USB_DEV_HS_CN_N") (class "Default")
      (node (ref "CN1") (pin "2") (pinfunction "DM_2") (pintype "passive"))
      (node (ref "U2") (pin "5") (pinfunction "D-_5") (pintype "passive"))
    )
    (net (code "22") (name "/USB_DEV_HS_CN_P") (class "Default")
      (node (ref "CN1") (pin "3") (pinfunction "DP_3") (pintype "passive"))
      (node (ref "U2") (pin "6") (pinfunction "D+_6") (pintype "passive"))
    )
    (net (code "23") (name "/USB_DEV_HS_N") (class "Default")
      (node (ref "U2") (pin "2") (pinfunction "D-_2") (pintype "passive"))
      (node (ref "U5") (pin "R14") (pinfunction "USB_DEV_HS_N/PB14_R14") (pintype "passive"))
    )
    (net (code "24") (name "/USB_DEV_HS_P") (class "Default")
      (node (ref "U2") (pin "1") (pinfunction "D+_1") (pintype "passive"))
      (node (ref "U5") (pin "R15") (pinfunction "USB_DEV_HS_P/PB15_R15") (pintype "passive"))
    )
    (net (code "25") (name "3V3") (class "Default")
      (node (ref "CN4") (pin "3") (pinfunction "3_3") (pintype "passive"))
      (node (ref "R19") (pin "2") (pinfunction "2_2") (pintype "passive"))
    )
    (net (code "26") (name "3V3_STLK") (class "Default")
      (node (ref "C13") (pin "2") (pinfunction "2_2") (pintype "passive"))
      (node (ref "C14") (pin "2") (pinfunction "2_2") (pintype "passive"))
      (node (ref "C15") (pin "2") (pinfunction "2_2") (pintype "passive"))
      (node (ref "C16") (pin "2") (pinfunction "2_2") (pintype "passive"))
      (node (ref "C17") (pin "2") (pinfunction "2_2") (pintype "passive"))
      (node (ref "C18") (pin "2") (pinfunction "2_2") (pintype "passive"))
      (node (ref "C21") (pin "2") (pinfunction "2_2") (pintype "passive"))
      (node (ref "C22") (pin "2") (pinfunction "2_2") (pintype "passive"))
      (node (ref "C23") (pin "2") (pinfunction "2_2") (pintype "passive"))
      (node (ref "C24") (pin "2") (pinfunction "2_2") (pintype "passive"))
      (node (ref "C25") (pin "2") (pinfunction "2_2") (pintype "passive"))
      (node (ref "C26") (pin "2") (pinfunction "2_2") (pintype "passive"))
      (node (ref "C27") (pin "2") (pinfunction "2_2") (pintype "passive"))
      (node (ref "C28") (pin "2") (pinfunction "2_2") (pintype "passive"))
      (node (ref "C29") (pin "2") (pinfunction "2_2") (pintype "passive"))
      (node (ref "C31") (pin "2") (pinfunction "2_2") (pintype "passive"))
      (node (ref "C32") (pin "2") (pinfunction "2_2") (pintype "passive"))
      (node (ref "C33") (pin "2") (pinfunction "2_2") (pintype "passive"))
      (node (ref "C6") (pin "2") (pinfunction "2_2") (pintype "passive"))
      (node (ref "C7") (pin "2") (pinfunction "2_2") (pintype "passive"))
      (node (ref "C8") (pin "2") (pinfunction "2_2") (pintype "passive"))
      (node (ref "C9") (pin "2") (pinfunction "2_2") (pintype "passive"))
      (node (ref "CN2") (pin "1") (pinfunction "1_1") (pintype "passive"))
      (node (ref "LD1") (pin "4") (pinfunction "YellowGreen_anode_4") (pintype "passive"))
      (node (ref "R14") (pin "1") (pinfunction "1_1") (pintype "passive"))
      (node (ref "R24") (pin "1") (pinfunction "1_1") (pintype "passive"))
      (node (ref "U5") (pin "C1") (pinfunction "VBAT_C1") (pintype "passive"))
      (node (ref "U5") (pin "C5") (pinfunction "VDD_C5") (pintype "passive"))
      (node (ref "U5") (pin "C7") (pinfunction "VDD_C7") (pintype "passive"))
      (node (ref "U5") (pin "C8") (pinfunction "VDD_C8") (pintype "passive"))
      (node (ref "U5") (pin "C9") (pinfunction "VDD_C9") (pintype "passive"))
      (node (ref "U5") (pin "F3") (pinfunction "VDD_F3") (pintype "passive"))
      (node (ref "U5") (pin "G13") (pinfunction "VDD_G13") (pintype "passive"))
      (node (ref "U5") (pin "G3") (pinfunction "VDD_G3") (pintype "passive"))
      (node (ref "U5") (pin "H13") (pinfunction "VDD_H13") (pintype "passive"))
      (node (ref "U5") (pin "J12") (pinfunction "VDD_J12") (pintype "passive"))
      (node (ref "U5") (pin "J13") (pinfunction "VDD_J13") (pintype "passive"))
      (node (ref "U5") (pin "K4") (pinfunction "VDD_K4") (pintype "passive"))
      (node (ref "U5") (pin "N10") (pinfunction "VDD_N10") (pintype "passive"))
      (node (ref "U5") (pin "N8") (pinfunction "VDD_N8") (pintype "passive"))
      (node (ref "U5") (pin "N9") (pinfunction "VDD_N9") (pintype "passive"))
      (node (ref "U5") (pin "P1") (pinfunction "VREF+_P1") (pintype "passive"))
      (node (ref "U5") (pin "R1") (pinfunction "VDDA_R1") (pintype "passive"))
      (node (ref "U7") (pin "5") (pinfunction "Vout_5") (pintype "passive"))
      (node (ref "X1") (pin "4") (pinfunction "VDD_4") (pintype "passive"))
    )
    (net (code "27") (name "5V") (class "Default")
      (node (ref "R12") (pin "1") (pinfunction "1_1") (pintype "passive"))
    )
    (net (code "28") (name "5V_USB_CHGR") (class "Default")
      (node (ref "C11") (pin "2") (pinfunction "2_2") (pintype "passive"))
      (node (ref "C2") (pin "2") (pinfunction "2_2") (pintype "passive"))
      (node (ref "CN1") (pin "1") (pinfunction "VBUS_1") (pintype "passive"))
      (node (ref "D1") (pin "1") (pinfunction "A_1") (pintype "passive"))
      (node (ref "R1") (pin "2") (pinfunction "2_2") (pintype "passive"))
      (node (ref "R6") (pin "2") (pinfunction "2_2") (pintype "passive"))
      (node (ref "U3") (pin "1") (pinfunction "IO1_1") (pintype "passive"))
      (node (ref "U4") (pin "5") (pinfunction "IN_5") (pintype "passive"))
    )
    (net (code "29") (name "5V_USB_STLK") (class "Default")
      (node (ref "C5") (pin "2") (pinfunction "2_2") (pintype "passive"))
      (node (ref "U4") (pin "1") (pinfunction "OUT_1") (pintype "passive"))
    )
    (net (code "30") (name "5V_VIN") (class "Default")
      (node (ref "D3") (pin "1") (pinfunction "A_1") (pintype "passive"))
    )
    (net (code "31") (name "E5V") (class "Default")
      (node (ref "D2") (pin "1") (pinfunction "A_1") (pintype "passive"))
    )
    (net (code "32") (name "GND") (class "Default")
      (node (ref "C1") (pin "1") (pinfunction "1_1") (pintype "passive"))
      (node (ref "C10") (pin "1") (pinfunction "1_1") (pintype "passive"))
      (node (ref "C11") (pin "1") (pinfunction "1_1") (pintype "passive"))
      (node (ref "C12") (pin "1") (pinfunction "1_1") (pintype "passive"))
      (node (ref "C13") (pin "1") (pinfunction "1_1") (pintype "passive"))
      (node (ref "C14") (pin "1") (pinfunction "1_1") (pintype "passive"))
      (node (ref "C15") (pin "1") (pinfunction "1_1") (pintype "passive"))
      (node (ref "C16") (pin "1") (pinfunction "1_1") (pintype "passive"))
      (node (ref "C17") (pin "1") (pinfunction "1_1") (pintype "passive"))
      (node (ref "C18") (pin "1") (pinfunction "1_1") (pintype "passive"))
      (node (ref "C19") (pin "1") (pinfunction "1_1") (pintype "passive"))
      (node (ref "C2") (pin "1") (pinfunction "1_1") (pintype "passive"))
      (node (ref "C20") (pin "1") (pinfunction "1_1") (pintype "passive"))
      (node (ref "C21") (pin "1") (pinfunction "1_1") (pintype "passive"))
      (node (ref "C22") (pin "1") (pinfunction "1_1") (pintype "passive"))
      (node (ref "C23") (pin "1") (pinfunction "1_1") (pintype "passive"))
      (node (ref "C24") (pin "1") (pinfunction "1_1") (pintype "passive"))
      (node (ref "C25") (pin "1") (pinfunction "1_1") (pintype "passive"))
      (node (ref "C26") (pin "1") (pinfunction "1_1") (pintype "passive"))
      (node (ref "C27") (pin "1") (pinfunction "1_1") (pintype "passive"))
      (node (ref "C28") (pin "1") (pinfunction "1_1") (pintype "passive"))
      (node (ref "C29") (pin "1") (pinfunction "1_1") (pintype "passive"))
      (node (ref "C3") (pin "1") (pinfunction "1_1") (pintype "passive"))
      (node (ref "C30") (pin "1") (pinfunction "1_1") (pintype "passive"))
      (node (ref "C31") (pin "1") (pinfunction "1_1") (pintype "passive"))
      (node (ref "C32") (pin "1") (pinfunction "1_1") (pintype "passive"))
      (node (ref "C33") (pin "1") (pinfunction "1_1") (pintype "passive"))
      (node (ref "C4") (pin "1") (pinfunction "1_1") (pintype "passive"))
      (node (ref "C5") (pin "1") (pinfunction "1_1") (pintype "passive"))
      (node (ref "C6") (pin "1") (pinfunction "1_1") (pintype "passive"))
      (node (ref "C7") (pin "1") (pinfunction "1_1") (pintype "passive"))
      (node (ref "C8") (pin "1") (pinfunction "1_1") (pintype "passive"))
      (node (ref "C9") (pin "1") (pinfunction "1_1") (pintype "passive"))
      (node (ref "CN1") (pin "10") (pinfunction "EXP_10") (pintype "passive"))
      (node (ref "CN1") (pin "11") (pinfunction "EXP_11") (pintype "passive"))
      (node (ref "CN1") (pin "5") (pinfunction "GND_5") (pintype "passive"))
      (node (ref "CN1") (pin "6") (pinfunction "Shield_6") (pintype "passive"))
      (node (ref "CN1") (pin "7") (pinfunction "Shield_7") (pintype "passive"))
      (node (ref "CN1") (pin "8") (pinfunction "Shield_8") (pintype "passive"))
      (node (ref "CN1") (pin "9") (pinfunction "Shield_9") (pintype "passive"))
      (node (ref "CN11") (pin "1") (pinfunction "COMMON_1") (pintype "passive"))
      (node (ref "CN11") (pin "2") (pinfunction "NO_2") (pintype "passive"))
      (node (ref "CN12") (pin "1") (pinfunction "COMMON_1") (pintype "passive"))
      (node (ref "CN12") (pin "2") (pinfunction "NO_2") (pintype "passive"))
      (node (ref "CN2") (pin "3") (pinfunction "3_3") (pintype "passive"))
      (node (ref "CN4") (pin "5") (pinfunction "5_5") (pintype "passive"))
      (node (ref "CN4") (pin "7") (pinfunction "7_7") (pintype "passive"))
      (node (ref "JP1") (pin "1") (pinfunction "COMMON_1") (pintype "passive"))
      (node (ref "LD1") (pin "1") (pinfunction "RED_cathode_1") (pintype "passive"))
      (node (ref "R11") (pin "1") (pinfunction "1_1") (pintype "passive"))
      (node (ref "R15") (pin "1") (pinfunction "1_1") (pintype "passive"))
      (node (ref "R16") (pin "2") (pinfunction "2_2") (pintype "passive"))
      (node (ref "R17") (pin "1") (pinfunction "1_1") (pintype "passive"))
      (node (ref "R21") (pin "1") (pinfunction "1_1") (pintype "passive"))
      (node (ref "R5") (pin "1") (pinfunction "1_1") (pintype "passive"))
      (node (ref "R8") (pin "2") (pinfunction "2_2") (pintype "passive"))
      (node (ref "U1") (pin "2") (pinfunction "GND_2") (pintype "passive"))
      (node (ref "U2") (pin "3") (pinfunction "GND_3") (pintype "passive"))
      (node (ref "U3") (pin "2") (pinfunction "GND_2") (pintype "passive"))
      (node (ref "U4") (pin "2") (pinfunction "GND_2") (pintype "passive"))
      (node (ref "U5") (pin "D5") (pinfunction "VSS_D5") (pintype "passive"))
      (node (ref "U5") (pin "D7") (pinfunction "VSS_D7") (pintype "passive"))
      (node (ref "U5") (pin "D8") (pinfunction "VSS_D8") (pintype "passive"))
      (node (ref "U5") (pin "D9") (pinfunction "VSS_D9") (pintype "passive"))
      (node (ref "U5") (pin "F10") (pinfunction "VSS_F10") (pintype "passive"))
      (node (ref "U5") (pin "F12") (pinfunction "VSS_F12") (pintype "passive"))
      (node (ref "U5") (pin "F2") (pinfunction "VSS_F2") (pintype "passive"))
      (node (ref "U5") (pin "F6") (pinfunction "VSS_F6") (pintype "passive"))
      (node (ref "U5") (pin "F7") (pinfunction "VSS_F7") (pintype "passive"))
      (node (ref "U5") (pin "F8") (pinfunction "VSS_F8") (pintype "passive"))
      (node (ref "U5") (pin "F9") (pinfunction "VSS_F9") (pintype "passive"))
      (node (ref "U5") (pin "G10") (pinfunction "VSS_G10") (pintype "passive"))
      (node (ref "U5") (pin "G12") (pinfunction "VSS_G12") (pintype "passive"))
      (node (ref "U5") (pin "G2") (pinfunction "VSS_G2") (pintype "passive"))
      (node (ref "U5") (pin "G6") (pinfunction "VSS_G6") (pintype "passive"))
      (node (ref "U5") (pin "G7") (pinfunction "VSS_G7") (pintype "passive"))
      (node (ref "U5") (pin "G8") (pinfunction "VSS_G8") (pintype "passive"))
      (node (ref "U5") (pin "G9") (pinfunction "VSS_G9") (pintype "passive"))
      (node (ref "U5") (pin "H10") (pinfunction "VSS_H10") (pintype "passive"))
      (node (ref "U5") (pin "H12") (pinfunction "VSS_H12") (pintype "passive"))
      (node (ref "U5") (pin "H6") (pinfunction "VSS_H6") (pintype "passive"))
      (node (ref "U5") (pin "H7") (pinfunction "VSS_H7") (pintype "passive"))
      (node (ref "U5") (pin "H8") (pinfunction "VSS_H8") (pintype "passive"))
      (node (ref "U5") (pin "H9") (pinfunction "VSS_H9") (pintype "passive"))
      (node (ref "U5") (pin "J10") (pinfunction "VSS_J10") (pintype "passive"))
      (node (ref "U5") (pin "J6") (pinfunction "VSS_J6") (pintype "passive"))
      (node (ref "U5") (pin "J7") (pinfunction "VSS_J7") (pintype "passive"))
      (node (ref "U5") (pin "J8") (pinfunction "VSS_J8") (pintype "passive"))
      (node (ref "U5") (pin "J9") (pinfunction "VSS_J9") (pintype "passive"))
      (node (ref "U5") (pin "K10") (pinfunction "VSS_K10") (pintype "passive"))
      (node (ref "U5") (pin "K6") (pinfunction "VSS_K6") (pintype "passive"))
      (node (ref "U5") (pin "K7") (pinfunction "VSS_K7") (pintype "passive"))
      (node (ref "U5") (pin "K8") (pinfunction "VSS_K8") (pintype "passive"))
      (node (ref "U5") (pin "K9") (pinfunction "VSS_K9") (pintype "passive"))
      (node (ref "U5") (pin "M1") (pinfunction "VSSA_M1") (pintype "passive"))
      (node (ref "U5") (pin "M8") (pinfunction "VSS_M8") (pintype "passive"))
      (node (ref "U5") (pin "M9") (pinfunction "VSS_M9") (pintype "passive"))
      (node (ref "U5") (pin "N1") (pinfunction "VREF-_N1") (pintype "passive"))
      (node (ref "U6") (pin "2") (pinfunction "GND_2") (pintype "passive"))
      (node (ref "U7") (pin "2") (pinfunction "GND_2") (pintype "passive"))
      (node (ref "U8") (pin "2") (pinfunction "GND_2") (pintype "passive"))
      (node (ref "X1") (pin "2") (pinfunction "GND_2") (pintype "passive"))
    )
    (net (code "33") (name "Net-(D1-K)") (class "Default")
      (node (ref "C19") (pin "2") (pinfunction "2_2") (pintype "passive"))
      (node (ref "C20") (pin "2") (pinfunction "2_2") (pintype "passive"))
      (node (ref "D1") (pin "2") (pinfunction "K_2") (pintype "passive"))
      (node (ref "D2") (pin "2") (pinfunction "K_2") (pintype "passive"))
      (node (ref "D3") (pin "2") (pinfunction "K_2") (pintype "passive"))
      (node (ref "U7") (pin "1") (pinfunction "Vin_1") (pintype "passive"))
      (node (ref "U7") (pin "3") (pinfunction "CE_3") (pintype "passive"))
    )
    (net (code "34") (name "Net-(JP1-NO)") (class "Default")
      (node (ref "C1") (pin "2") (pinfunction "2_2") (pintype "passive"))
      (node (ref "JP1") (pin "2") (pinfunction "NO_2") (pintype "passive"))
      (node (ref "U5") (pin "J1") (pinfunction "NRST_J1") (pintype "passive"))
    )
    (net (code "35") (name "Net-(JP3-NO)") (class "Default")
      (node (ref "JP3") (pin "2") (pinfunction "NO_2") (pintype "passive"))
      (node (ref "R18") (pin "1") (pinfunction "1_1") (pintype "passive"))
    )
    (net (code "36") (name "Net-(LD1-Red_anode)") (class "Default")
      (node (ref "LD1") (pin "2") (pinfunction "Red_anode_2") (pintype "passive"))
      (node (ref "R3") (pin "1") (pinfunction "1_1") (pintype "passive"))
    )
    (net (code "37") (name "Net-(LD1-YellowGreen_cathode)") (class "Default")
      (node (ref "LD1") (pin "3") (pinfunction "YellowGreen_cathode_3") (pintype "passive"))
      (node (ref "R2") (pin "1") (pinfunction "1_1") (pintype "passive"))
    )
    (net (code "38") (name "Net-(LD4-Pad1)") (class "Default")
      (node (ref "LD4") (pin "1") (pintype "passive"))
      (node (ref "R1") (pin "1") (pinfunction "1_1") (pintype "passive"))
    )
    (net (code "39") (name "Net-(U4-~{FAULT})") (class "Default")
      (node (ref "LD4") (pin "2") (pintype "passive"))
      (node (ref "R6") (pin "1") (pinfunction "1_1") (pintype "passive"))
      (node (ref "U4") (pin "3") (pinfunction "~{FAULT}_3") (pintype "passive"))
    )
    (net (code "40") (name "Net-(U5A-BOOT0)") (class "Default")
      (node (ref "R17") (pin "2") (pinfunction "2_2") (pintype "passive"))
      (node (ref "U5") (pin "D6") (pinfunction "BOOT0_D6") (pintype "passive"))
    )
    (net (code "41") (name "Net-(U5A-OSC_IN{slash}PH0)") (class "Default")
      (node (ref "R20") (pin "2") (pinfunction "2_2") (pintype "passive"))
      (node (ref "U5") (pin "G1") (pinfunction "OSC_IN/PH0_G1") (pintype "passive"))
    )
    (net (code "42") (name "Net-(U5A-PDR_ON)") (class "Default")
      (node (ref "R14") (pin "2") (pinfunction "2_2") (pintype "passive"))
      (node (ref "U5") (pin "C6") (pinfunction "PDR_ON_C6") (pintype "passive"))
    )
    (net (code "43") (name "Net-(U5A-REXT_OTGPHY)") (class "Default")
      (node (ref "R5") (pin "2") (pinfunction "2_2") (pintype "passive"))
      (node (ref "U5") (pin "J15") (pinfunction "REXT_OTGPHY_J15") (pintype "passive"))
    )
    (net (code "44") (name "Net-(U5A-STLK_MCO{slash}PA8)") (class "Default")
      (node (ref "R4") (pin "1") (pinfunction "1_1") (pintype "passive"))
      (node (ref "U5") (pin "F15") (pinfunction "STLK_MCO/PA8_F15") (pintype "passive"))
    )
    (net (code "45") (name "Net-(U5A-T_VCC_AIN{slash}PA0)") (class "Default")
      (node (ref "R16") (pin "1") (pinfunction "1_1") (pintype "passive"))
      (node (ref "R19") (pin "1") (pinfunction "1_1") (pintype "passive"))
      (node (ref "U5") (pin "N3") (pinfunction "T_VCC_AIN/PA0_N3") (pintype "passive"))
    )
    (net (code "46") (name "Net-(U5A-V12_OTGPHY)") (class "Default")
      (node (ref "C4") (pin "2") (pinfunction "2_2") (pintype "passive"))
      (node (ref "U5") (pin "J14") (pinfunction "V12_OTGPHY_J14") (pintype "passive"))
    )
    (net (code "47") (name "Net-(U5B-BYPASS-REG)") (class "Default")
      (node (ref "R21") (pin "2") (pinfunction "2_2") (pintype "passive"))
      (node (ref "U5") (pin "L4") (pinfunction "BYPASS-REG_L4") (pintype "passive"))
    )
    (net (code "48") (name "Net-(U5B-VCAP1)") (class "Default")
      (node (ref "C12") (pin "2") (pinfunction "2_2") (pintype "passive"))
      (node (ref "U5") (pin "M10") (pinfunction "VCAP1_M10") (pintype "passive"))
    )
    (net (code "49") (name "Net-(U5B-VCAP2)") (class "Default")
      (node (ref "C10") (pin "2") (pinfunction "2_2") (pintype "passive"))
      (node (ref "U5") (pin "F13") (pinfunction "VCAP2_F13") (pintype "passive"))
    )
    (net (code "50") (name "Net-(U7-BYPASS)") (class "Default")
      (node (ref "C30") (pin "2") (pinfunction "2_2") (pintype "passive"))
      (node (ref "U7") (pin "4") (pinfunction "BYPASS_4") (pintype "passive"))
    )
    (net (code "51") (name "Net-(X1-EN)") (class "Default")
      (node (ref "R24") (pin "2") (pinfunction "2_2") (pintype "passive"))
      (node (ref "X1") (pin "1") (pinfunction "EN_1") (pintype "passive"))
    )
    (net (code "52") (name "Net-(X1-OUT)") (class "Default")
      (node (ref "R20") (pin "1") (pinfunction "1_1") (pintype "passive"))
      (node (ref "X1") (pin "3") (pinfunction "OUT_3") (pintype "passive"))
    )
    (net (code "53") (name "unconnected-(CN1-ID-Pad4)") (class "Default")
      (node (ref "CN1") (pin "4") (pinfunction "ID_4") (pintype "passive+no_connect"))
    )
    (net (code "54") (name "unconnected-(CN4-Pad1)") (class "Default")
      (node (ref "CN4") (pin "1") (pinfunction "1_1") (pintype "passive+no_connect"))
    )
    (net (code "55") (name "unconnected-(CN4-Pad2)") (class "Default")
      (node (ref "CN4") (pin "2") (pinfunction "2_2") (pintype "passive+no_connect"))
    )
    (net (code "56") (name "unconnected-(CN4-Pad9)") (class "Default")
      (node (ref "CN4") (pin "9") (pinfunction "9_9") (pintype "passive+no_connect"))
    )
    (net (code "57") (name "unconnected-(U2-NC-Pad4)") (class "Default")
      (node (ref "U2") (pin "4") (pinfunction "NC_4") (pintype "passive+no_connect"))
    )
    (net (code "58") (name "unconnected-(U5A-HW_TYP_0{slash}PI4-PadD4)") (class "Default")
      (node (ref "U5") (pin "D4") (pinfunction "HW_TYP_0/PI4_D4") (pintype "passive+no_connect"))
    )
    (net (code "59") (name "unconnected-(U5A-HW_TYP_1{slash}PI5-PadC4)") (class "Default")
      (node (ref "U5") (pin "C4") (pinfunction "HW_TYP_1/PI5_C4") (pintype "passive+no_connect"))
    )
    (net (code "60") (name "unconnected-(U5A-OSC_OUT{slash}PH1-PadH1)") (class "Default")
      (node (ref "U5") (pin "H1") (pinfunction "OSC_OUT/PH1_H1") (pintype "passive+no_connect"))
    )
    (net (code "61") (name "unconnected-(U5A-T_SW_DIR{slash}PA7-PadR3)") (class "Default")
      (node (ref "U5") (pin "R3") (pinfunction "T_SW_DIR/PA7_R3") (pintype "passive+no_connect"))
    )
  )
)
